# CAN_Transceiver_SN65HVD232D.net
KiCad netlist of a schematic drawn in Altium Designer
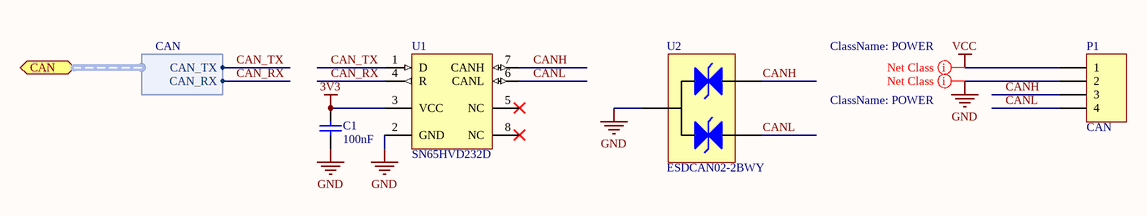
[diagram p0: CAN Transceiver SN65HVD232D.SchDoc]

(export (version "E")
  (design (tool "Eeschema 10.0.6"))
  (components
    (comp (ref "C1")
      (value "100nF")
      (footprint "agh_racing_2018:CAP_0603_IPC_MD")
      (description "Capacitor")
      (fields (field (name "Comment") "Cap"))
      (libsource (lib "agh_racing_2018") (part "Cap"))
    )
    (comp (ref "P1")
      (value "CAN")
      (footprint "agh_racing_2018:WIRE_PADS_4")
      (description "Header, 4-Pin")
      (libsource (lib "agh_racing_2018") (part "Header 4"))
    )
    (comp (ref "U1")
      (value "SN65HVD232D")
      (footprint "SOIC_8_IPC_MD")
      (fields (field (name "MANUFACTURER") "Texas Instruments"))
      (libsource (lib "agh_racing_2018") (part "SN65HVD232D"))
    )
    (comp (ref "U2")
      (value "ESDCAN02-2BWY")
      (footprint "SOT23_IPC_MD")
      (description "ESD CAN protection (2 transils)")
      (libsource (lib "agh_racing_2018") (part "ESDCAN02-2BWY"))
    )
  )
  (nets
    (net (code "2") (name "/CANH") (class "Default")
      (node (ref "P1") (pin "3") (pinfunction "3_3") (pintype "passive"))
      (node (ref "U1") (pin "7") (pinfunction "CANH_7") (pintype "bidirectional"))
      (node (ref "U2") (pin "1") (pinfunction "IN1_1") (pintype "passive"))
    )
    (net (code "3") (name "/CANL") (class "Default")
      (node (ref "P1") (pin "4") (pinfunction "4_4") (pintype "passive"))
      (node (ref "U1") (pin "6") (pinfunction "CANL_6") (pintype "bidirectional"))
      (node (ref "U2") (pin "2") (pinfunction "IN2_2") (pintype "passive"))
    )
    (net (code "4") (name "/CAN_RX") (class "Default")
      (node (ref "U1") (pin "4") (pinfunction "R_4") (pintype "output"))
    )
    (net (code "5") (name "/CAN_TX") (class "Default")
      (node (ref "U1") (pin "1") (pinfunction "D_1") (pintype "input"))
    )
    (net (code "7") (name "3V3") (class "Default")
      (node (ref "C1") (pin "2") (pinfunction "2_2") (pintype "passive"))
      (node (ref "U1") (pin "3") (pinfunction "VCC_3") (pintype "power_in"))
    )
    (net (code "8") (name "GND") (class "Default")
      (node (ref "C1") (pin "1") (pinfunction "1_1") (pintype "passive"))
      (node (ref "P1") (pin "2") (pinfunction "2_2") (pintype "passive"))
      (node (ref "U1") (pin "2") (pinfunction "GND_2") (pintype "power_in"))
      (node (ref "U2") (pin "3") (pinfunction "COM_3") (pintype "passive"))
    )
    (net (code "9") (name "VCC") (class "Default")
      (node (ref "P1") (pin "1") (pinfunction "1_1") (pintype "passive"))
    )
    (net (code "10") (name "unconnected-(U1-NC-Pad5)") (class "Default")
      (node (ref "U1") (pin "5") (pinfunction "NC_5") (pintype "passive+no_connect"))
    )
    (net (code "11") (name "unconnected-(U1-NC-Pad8)") (class "Default")
      (node (ref "U1") (pin "8") (pinfunction "NC_8") (pintype "passive+no_connect"))
    )
  )
)
